# mt3608.net
KiCad netlist of a schematic drawn in Altium Designer
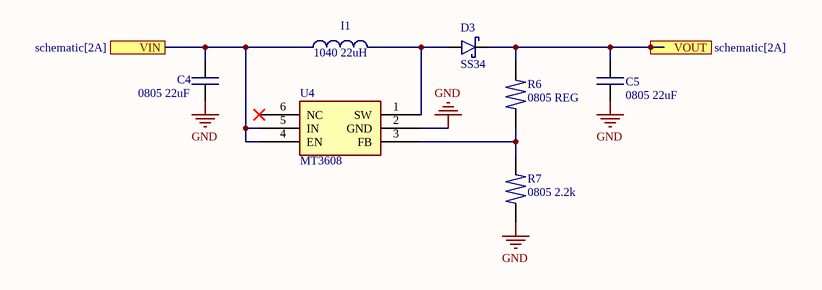
[diagram p0: mt3608.SchDoc]

(export (version "E")
  (design (tool "Eeschema 10.0.6"))
  (components
    (comp (ref "C4")
      (value "0805 22uF")
      (footprint "CAPACITOR 0805")
      (libsource (lib "Ceramic Capacitor") (part "CAPACITOR 0805"))
    )
    (comp (ref "C5")
      (value "0805 22uF")
      (footprint "CAPACITOR 0805")
      (libsource (lib "Ceramic Capacitor") (part "CAPACITOR 0805"))
    )
    (comp (ref "D3")
      (value "SS34")
      (footprint "SS34")
      (description "Rectifier Schottky 40V 3A SMC")
      (libsource (lib "Diode") (part "SS34"))
    )
    (comp (ref "I1") (value "1040 22uH") (footprint "1040") (libsource (lib "Inductor") (part "1040")))
    (comp (ref "R6")
      (value "0805 REG")
      (footprint "RESISTOR_0805")
      (libsource (lib "Resistors") (part "RESISTOR_0805"))
    )
    (comp (ref "R7")
      (value "0805 2.2k")
      (footprint "RESISTOR_0805")
      (libsource (lib "Resistors") (part "RESISTOR_0805"))
    )
    (comp (ref "U4")
      (value "MT3608")
      (footprint "MT3608")
      (description "IC BUCK STEP UP 2A SOT23-6")
      (libsource (lib "Voltage Regulators") (part "MT3608"))
    )
  )
  (nets
    (net (code "1") (name "/VIN") (class "Default")
      (node (ref "C4") (pin "2") (pinfunction "2_2") (pintype "passive"))
      (node (ref "I1") (pin "1") (pinfunction "1_1") (pintype "passive"))
      (node (ref "U4") (pin "4") (pinfunction "EN_4") (pintype "passive"))
      (node (ref "U4") (pin "5") (pinfunction "IN_5") (pintype "passive"))
    )
    (net (code "2") (name "/VOUT") (class "Default")
      (node (ref "C5") (pin "2") (pinfunction "2_2") (pintype "passive"))
      (node (ref "D3") (pin "2") (pintype "passive"))
      (node (ref "R6") (pin "2") (pinfunction "2_2") (pintype "passive"))
    )
    (net (code "3") (name "GND") (class "Default")
      (node (ref "C4") (pin "1") (pinfunction "1_1") (pintype "passive"))
      (node (ref "C5") (pin "1") (pinfunction "1_1") (pintype "passive"))
      (node (ref "R7") (pin "1") (pinfunction "1_1") (pintype "passive"))
      (node (ref "U4") (pin "2") (pinfunction "GND_2") (pintype "passive"))
    )
    (net (code "4") (name "Net-(U4-FB)") (class "Default")
      (node (ref "R6") (pin "1") (pinfunction "1_1") (pintype "passive"))
      (node (ref "R7") (pin "2") (pinfunction "2_2") (pintype "passive"))
      (node (ref "U4") (pin "3") (pinfunction "FB_3") (pintype "passive"))
    )
    (net (code "5") (name "Net-(U4-SW)") (class "Default")
      (node (ref "D3") (pin "1") (pinfunction "1_1") (pintype "passive"))
      (node (ref "I1") (pin "2") (pinfunction "2_2") (pintype "passive"))
      (node (ref "U4") (pin "1") (pinfunction "SW_1") (pintype "passive"))
    )
    (net (code "6") (name "unconnected-(U4-NC-Pad6)") (class "Default")
      (node (ref "U4") (pin "6") (pinfunction "NC_6") (pintype "passive+no_connect"))
    )
  )
)
